# FatLight.net
KiCad netlist of a schematic drawn in EAGLE
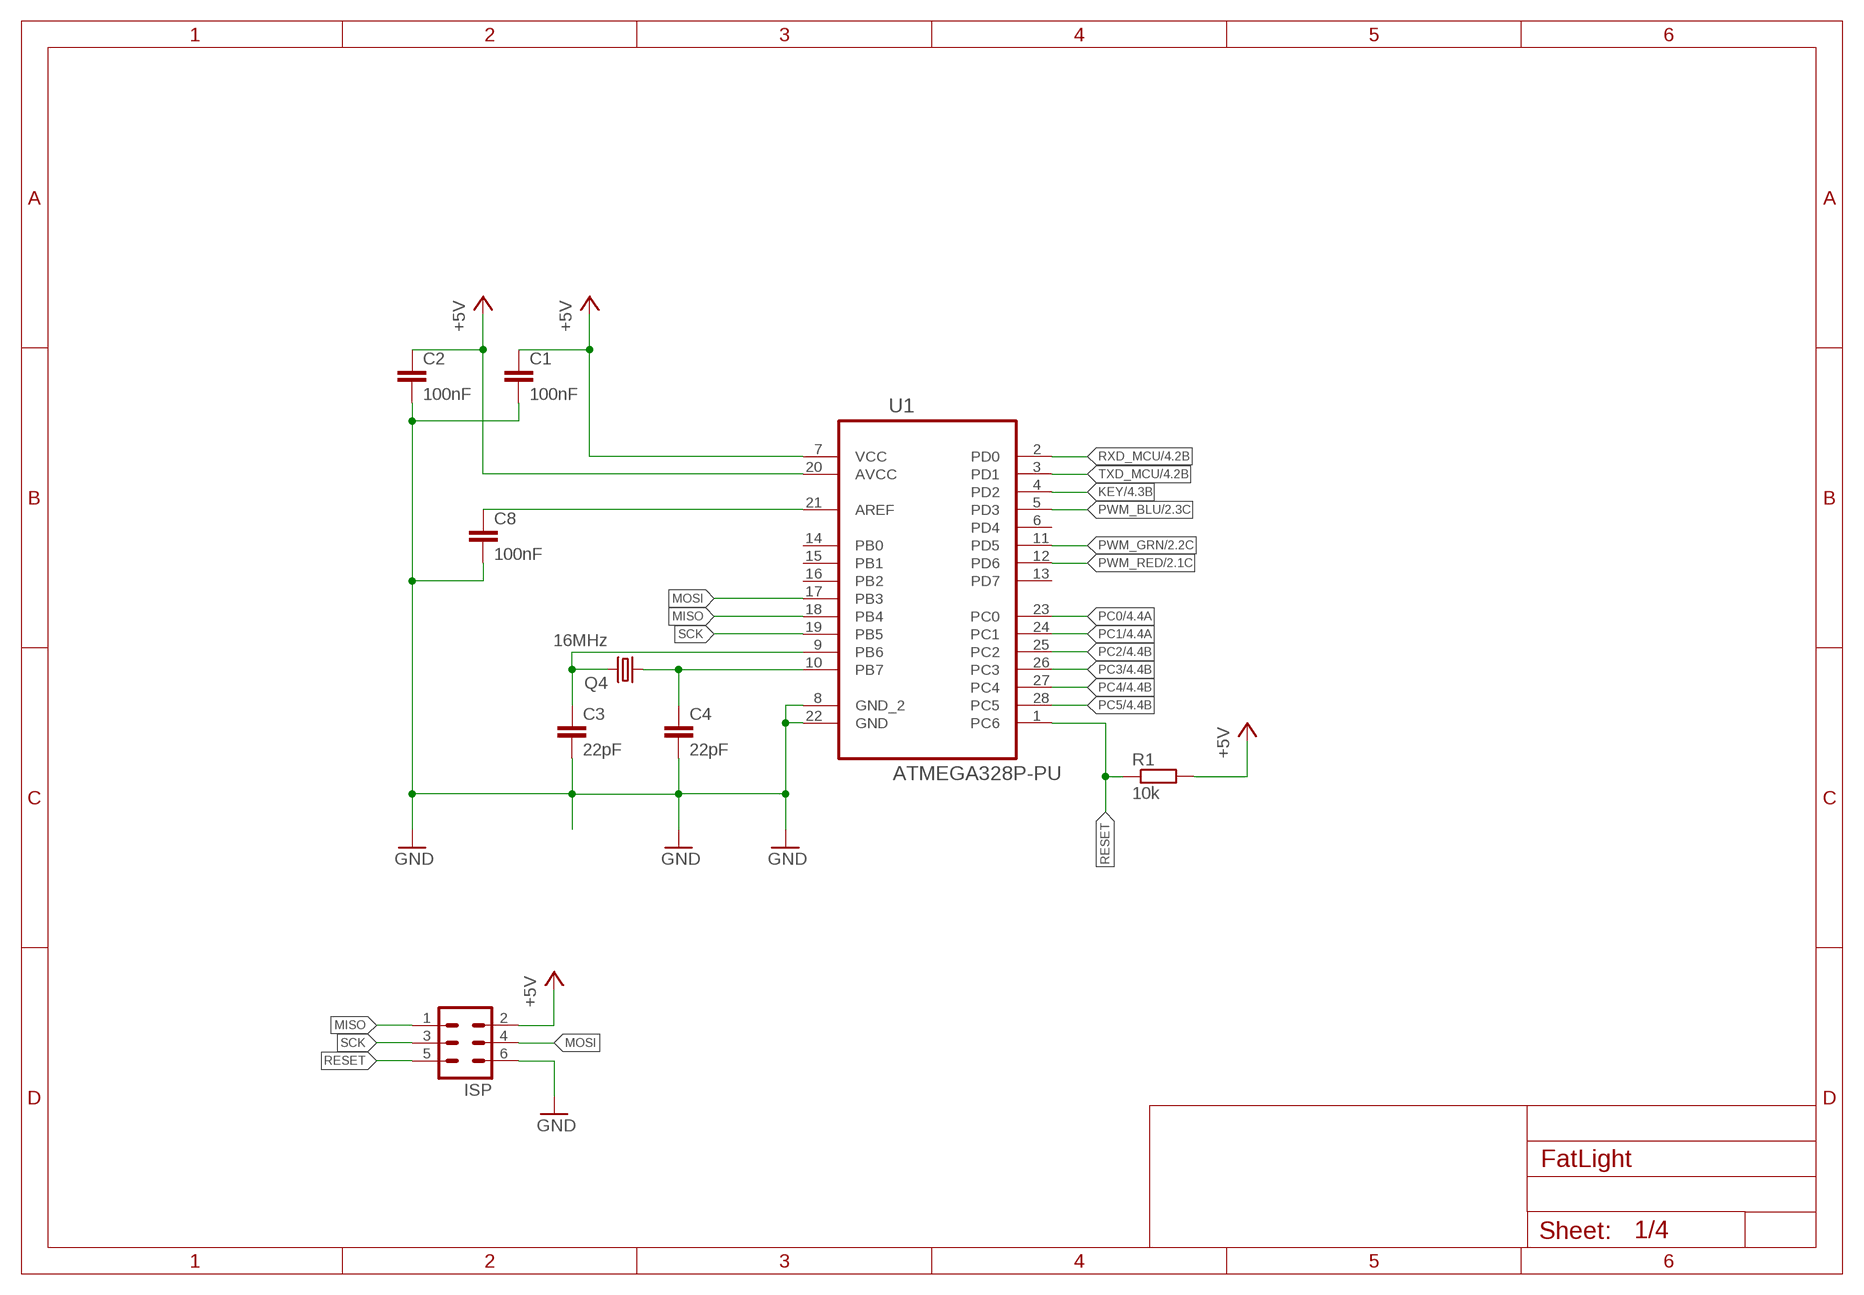
[diagram p0: schematic, sheet 1]
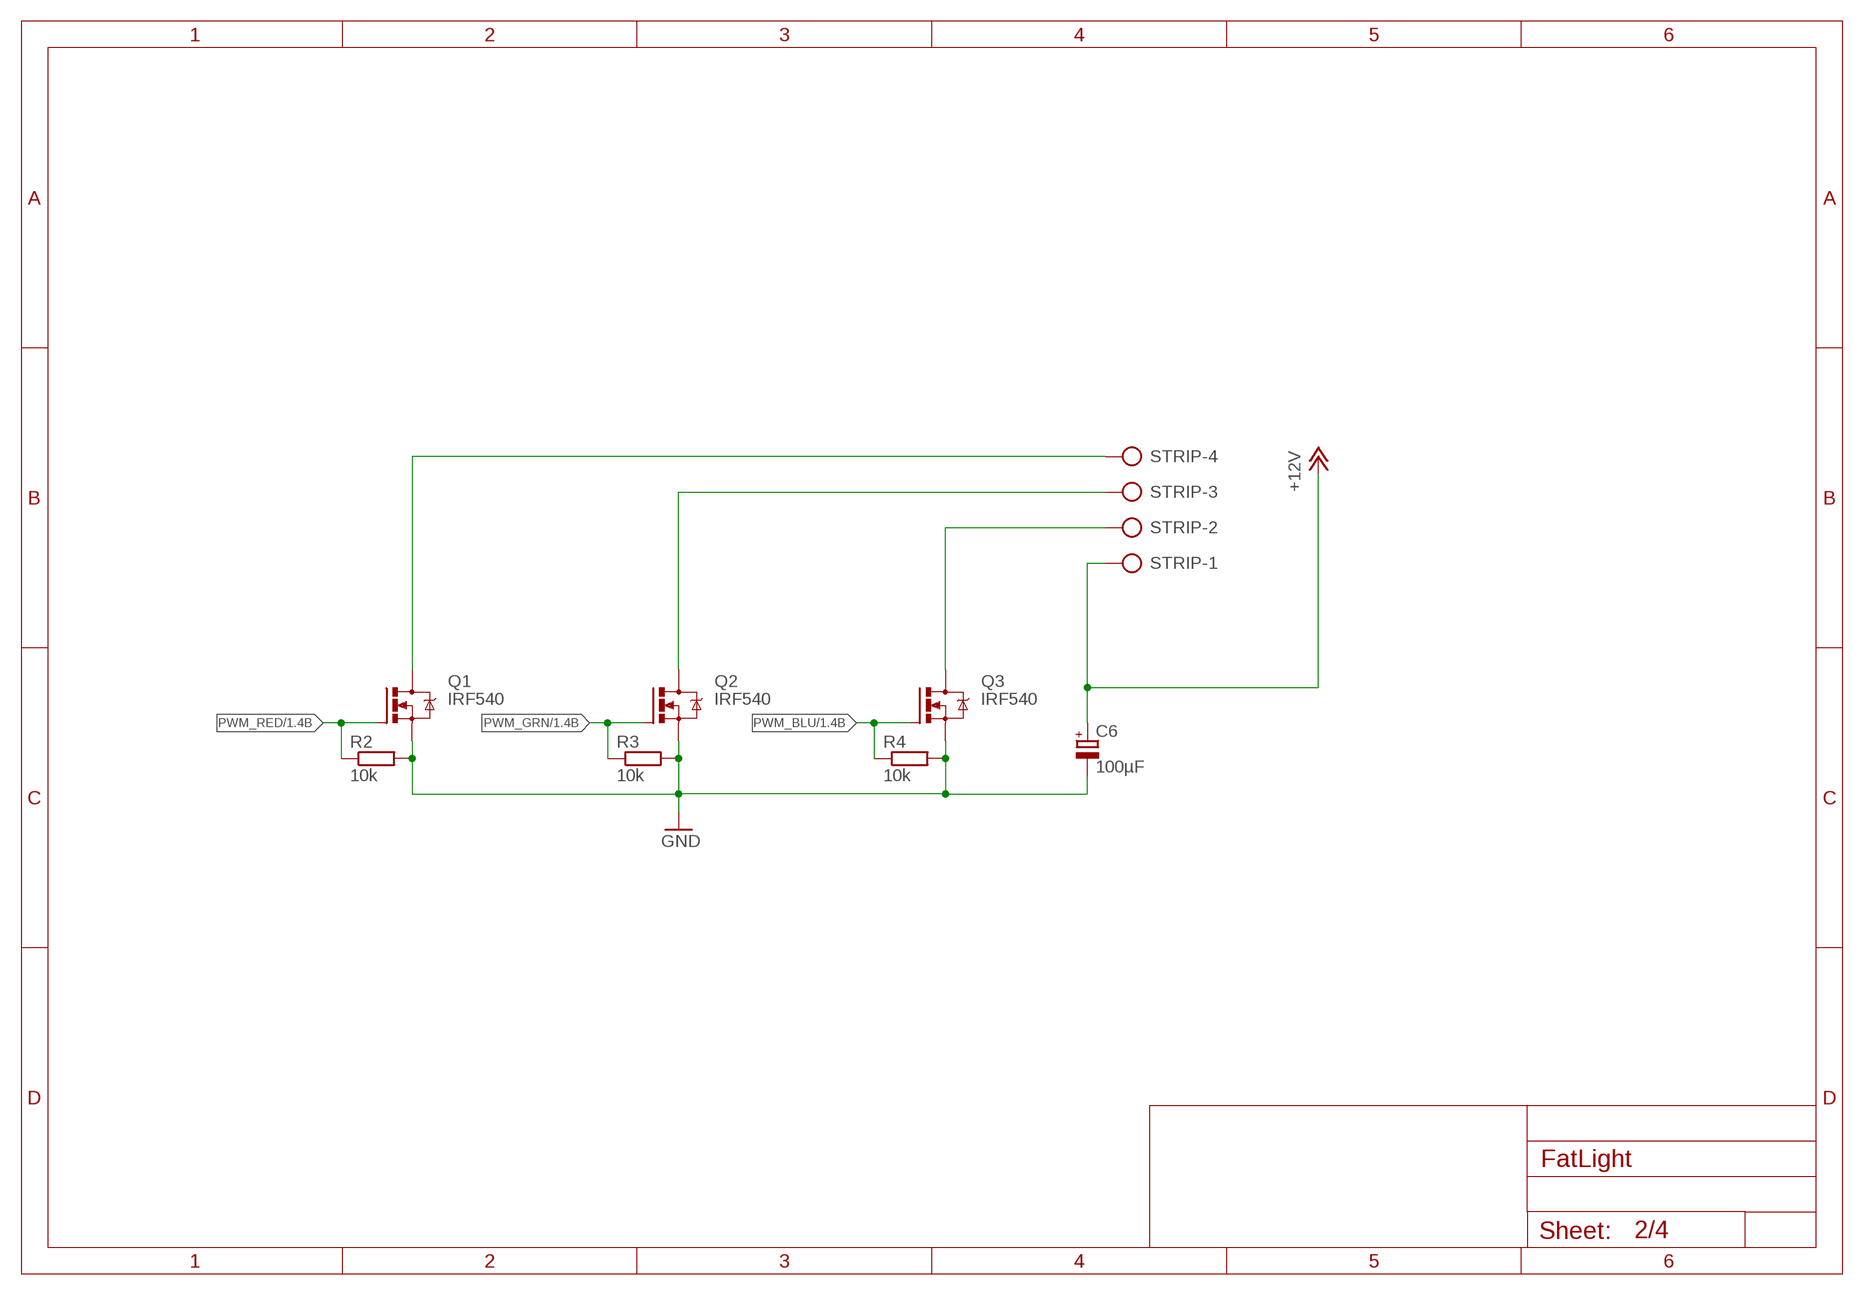
[diagram p1: schematic, sheet 2]
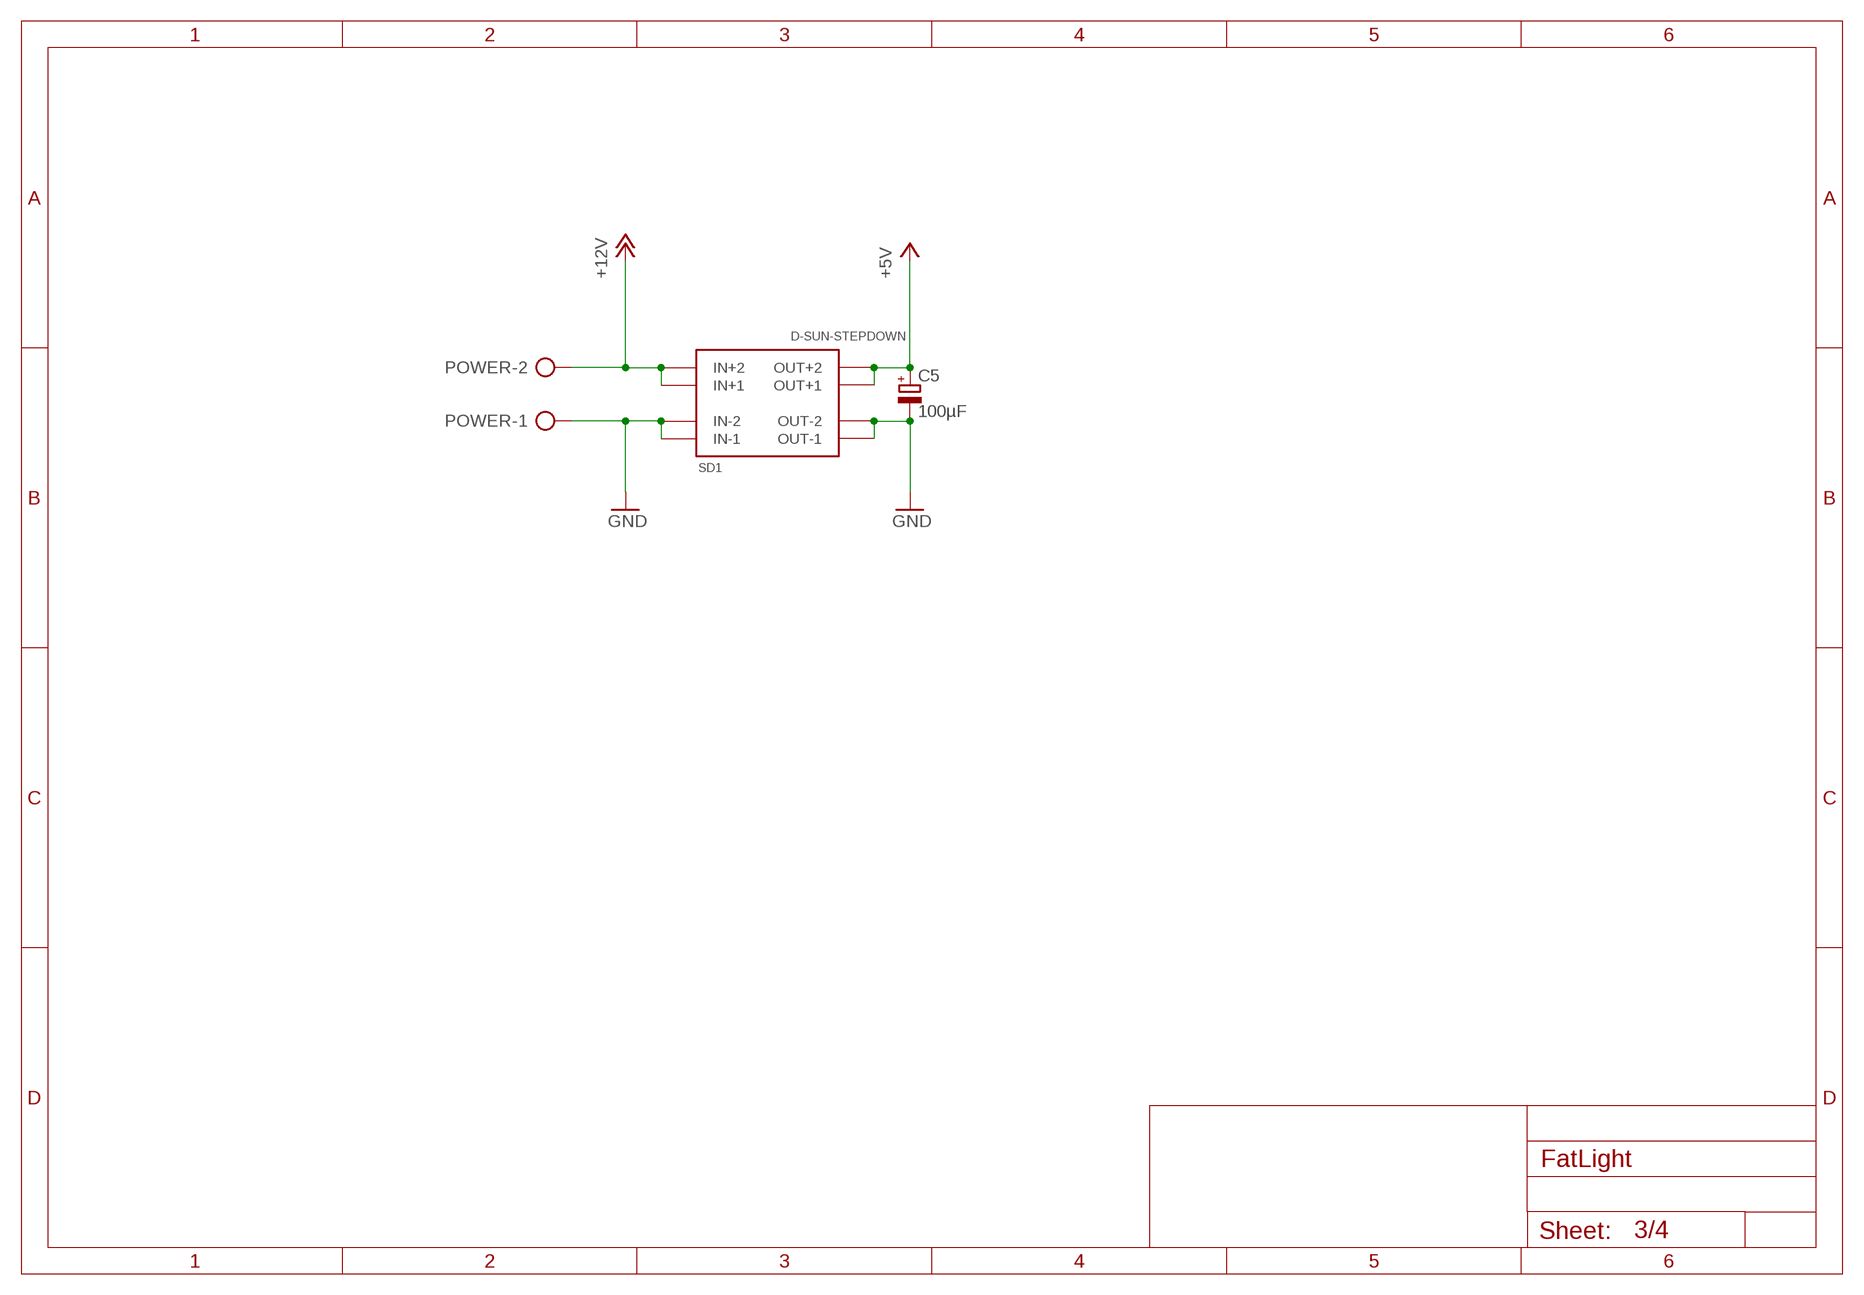
[diagram p2: schematic, sheet 3]
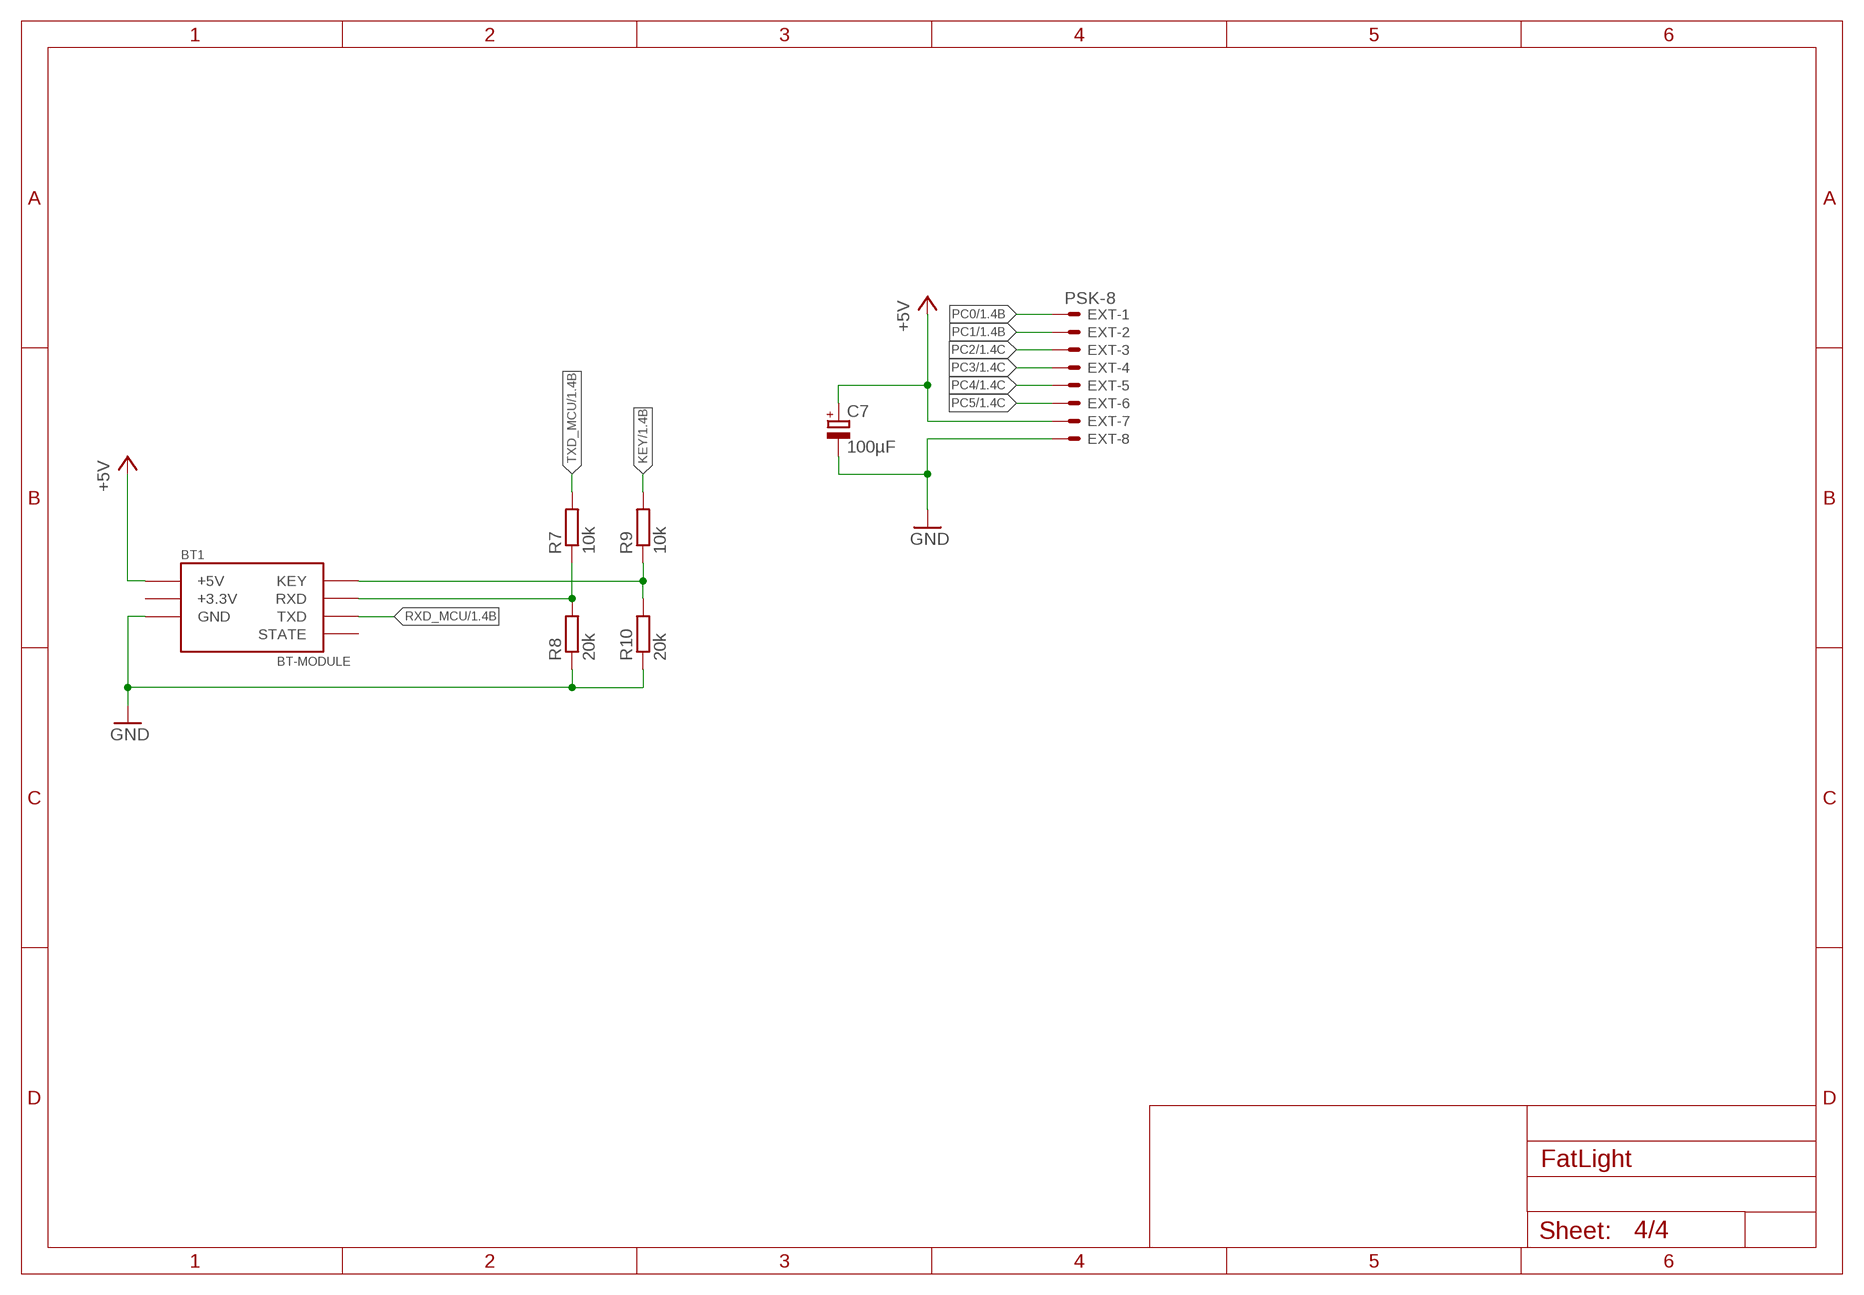
[diagram p3: schematic, sheet 4]

(export (version "E")
  (design (tool "Eeschema 10.0.6"))
  (components
    (comp (ref "BT1")
      (value "BT-MODULE")
      (footprint "eagle-import:HC-05-6PIN")
      (libsource (lib "eagle-import") (part "BT-MODULE"))
    )
    (comp (ref "C7")
      (value "100µF")
      (footprint "eagle-import:E2,5-5")
      (libsource (lib "eagle-import") (part "CPOL-EUE2.5-5"))
    )
    (comp (ref "EXT")
      (value "PSK-8")
      (footprint "eagle-import:22-23-2081")
      (fields (field (name "MF") "MOLEX") (field (name "MPN") "22-23-2081"))
      (libsource (lib "eagle-import") (part "22-23-2081"))
    )
    (comp (ref "R7")
      (value "10k")
      (footprint "eagle-import:0207_7")
      (libsource (lib "eagle-import") (part "R-EU_0207/7"))
    )
    (comp (ref "R8")
      (value "20k")
      (footprint "eagle-import:0207_7")
      (libsource (lib "eagle-import") (part "R-EU_0207/7"))
    )
    (comp (ref "R9")
      (value "10k")
      (footprint "eagle-import:0207_7")
      (libsource (lib "eagle-import") (part "R-EU_0207/7"))
    )
    (comp (ref "R10")
      (value "20k")
      (footprint "eagle-import:0207_7")
      (libsource (lib "eagle-import") (part "R-EU_0207/7"))
    )
    (comp (ref "C1")
      (value "100nF")
      (footprint "eagle-import:C025-025X050")
      (libsource (lib "eagle-import") (part "C-EU025-025X050"))
    )
    (comp (ref "C2")
      (value "100nF")
      (footprint "eagle-import:C025-025X050")
      (libsource (lib "eagle-import") (part "C-EU025-025X050"))
    )
    (comp (ref "C3")
      (value "22pF")
      (footprint "eagle-import:C025-025X050")
      (libsource (lib "eagle-import") (part "C-EU025-025X050"))
    )
    (comp (ref "C4")
      (value "22pF")
      (footprint "eagle-import:C025-025X050")
      (libsource (lib "eagle-import") (part "C-EU025-025X050"))
    )
    (comp (ref "C8")
      (value "100nF")
      (footprint "eagle-import:C025-025X050")
      (libsource (lib "eagle-import") (part "C-EU025-025X050"))
    )
    (comp (ref "ISP")
      (value "ML6")
      (footprint "eagle-import:ML6")
      (libsource (lib "eagle-import") (part "ML6"))
    )
    (comp (ref "Q4")
      (value "16MHz")
      (footprint "eagle-import:HC49_S")
      (libsource (lib "eagle-import") (part "CRYSTALHC49S"))
    )
    (comp (ref "R1")
      (value "10k")
      (footprint "eagle-import:0207_7")
      (libsource (lib "eagle-import") (part "R-EU_0207/7"))
    )
    (comp (ref "U1")
      (value "ATMEGA328P-PU")
      (footprint "eagle-import:DIP254P762X457-28")
      (libsource (lib "eagle-import") (part "ATMEGA328P-PU"))
    )
    (comp (ref "C5")
      (value "100µF")
      (footprint "eagle-import:E2,5-5")
      (libsource (lib "eagle-import") (part "CPOL-EUE2.5-5"))
    )
    (comp (ref "POWER")
      (value "AK500/2")
      (footprint "eagle-import:AK500_2")
      (libsource (lib "eagle-import") (part "AK500/2"))
    )
    (comp (ref "SD1")
      (value "D-SUN-STEPDOWN")
      (footprint "eagle-import:STEPDOWN-21X16")
      (libsource (lib "eagle-import") (part "D-SUN-STEPDOWN"))
    )
    (comp (ref "C6")
      (value "100µF")
      (footprint "eagle-import:E2,5-5")
      (libsource (lib "eagle-import") (part "CPOL-EUE2.5-5"))
    )
    (comp (ref "Q1")
      (value "IRF540")
      (footprint "eagle-import:TO220BV")
      (libsource (lib "eagle-import") (part "IRF540"))
    )
    (comp (ref "Q2")
      (value "IRF540")
      (footprint "eagle-import:TO220BV")
      (libsource (lib "eagle-import") (part "IRF540"))
    )
    (comp (ref "Q3")
      (value "IRF540")
      (footprint "eagle-import:TO220BV")
      (libsource (lib "eagle-import") (part "IRF540"))
    )
    (comp (ref "R2")
      (value "10k")
      (footprint "eagle-import:0207_7")
      (libsource (lib "eagle-import") (part "R-EU_0207/7"))
    )
    (comp (ref "R3")
      (value "10k")
      (footprint "eagle-import:0207_7")
      (libsource (lib "eagle-import") (part "R-EU_0207/7"))
    )
    (comp (ref "R4")
      (value "10k")
      (footprint "eagle-import:0207_7")
      (libsource (lib "eagle-import") (part "R-EU_0207/7"))
    )
    (comp (ref "STRIP")
      (value "AK500/4")
      (footprint "eagle-import:AK500_4")
      (libsource (lib "eagle-import") (part "AK500/4"))
    )
  )
  (nets
    (net (code "1") (name "+3.3V") (class "Default")
      (node (ref "BT1") (pin "+3.3V") (pinfunction "+3.3V_+3.3V") (pintype "power_in"))
    )
    (net (code "2") (name "+5V") (class "Default")
      (node (ref "BT1") (pin "+5V") (pinfunction "+5V_+5V") (pintype "power_in"))
      (node (ref "BT1") (pin "+5V1") (pinfunction "+5V_+5V1") (pintype "power_in"))
      (node (ref "C1") (pin "1") (pinfunction "1_1") (pintype "passive"))
      (node (ref "C2") (pin "1") (pinfunction "1_1") (pintype "passive"))
      (node (ref "C5") (pin "+") (pinfunction "+_+") (pintype "passive"))
      (node (ref "C7") (pin "+") (pinfunction "+_+") (pintype "passive"))
      (node (ref "EXT") (pin "7") (pinfunction "S_7") (pintype "passive"))
      (node (ref "ISP") (pin "2") (pinfunction "2_2") (pintype "passive"))
      (node (ref "R1") (pin "2") (pinfunction "2_2") (pintype "passive"))
      (node (ref "SD1") (pin "OUT+1") (pinfunction "OUT+1_OUT+1") (pintype "power_in"))
      (node (ref "SD1") (pin "OUT+2") (pinfunction "OUT+2_OUT+2") (pintype "power_in"))
      (node (ref "U1") (pin "20") (pinfunction "AVCC_20") (pintype "power_in"))
      (node (ref "U1") (pin "7") (pinfunction "VCC_7") (pintype "power_in"))
    )
    (net (code "3") (name "+12V") (class "Default")
      (node (ref "C6") (pin "+") (pinfunction "+_+") (pintype "passive"))
      (node (ref "POWER") (pin "2") (pinfunction "KL_2") (pintype "passive"))
      (node (ref "SD1") (pin "IN+1") (pinfunction "IN+1_IN+1") (pintype "power_in"))
      (node (ref "SD1") (pin "IN+2") (pinfunction "IN+2_IN+2") (pintype "power_in"))
      (node (ref "STRIP") (pin "1") (pinfunction "KL_1") (pintype "passive"))
    )
    (net (code "4") (name "GND") (class "Default")
      (node (ref "BT1") (pin "GND") (pinfunction "GND_GND") (pintype "power_in"))
      (node (ref "BT1") (pin "GND1") (pinfunction "GND_GND1") (pintype "power_in"))
      (node (ref "C1") (pin "2") (pinfunction "2_2") (pintype "passive"))
      (node (ref "C2") (pin "2") (pinfunction "2_2") (pintype "passive"))
      (node (ref "C3") (pin "2") (pinfunction "2_2") (pintype "passive"))
      (node (ref "C4") (pin "2") (pinfunction "2_2") (pintype "passive"))
      (node (ref "C5") (pin "-") (pinfunction "-_-") (pintype "passive"))
      (node (ref "C6") (pin "-") (pinfunction "-_-") (pintype "passive"))
      (node (ref "C7") (pin "-") (pinfunction "-_-") (pintype "passive"))
      (node (ref "C8") (pin "2") (pinfunction "2_2") (pintype "passive"))
      (node (ref "EXT") (pin "8") (pinfunction "S_8") (pintype "passive"))
      (node (ref "ISP") (pin "6") (pinfunction "6_6") (pintype "passive"))
      (node (ref "POWER") (pin "1") (pinfunction "KL_1") (pintype "passive"))
      (node (ref "Q1") (pin "S") (pinfunction "S_S") (pintype "passive"))
      (node (ref "Q2") (pin "S") (pinfunction "S_S") (pintype "passive"))
      (node (ref "Q3") (pin "S") (pinfunction "S_S") (pintype "passive"))
      (node (ref "R10") (pin "1") (pinfunction "1_1") (pintype "passive"))
      (node (ref "R2") (pin "2") (pinfunction "2_2") (pintype "passive"))
      (node (ref "R3") (pin "2") (pinfunction "2_2") (pintype "passive"))
      (node (ref "R4") (pin "2") (pinfunction "2_2") (pintype "passive"))
      (node (ref "R8") (pin "1") (pinfunction "1_1") (pintype "passive"))
      (node (ref "SD1") (pin "IN-1") (pinfunction "IN-1_IN-1") (pintype "power_in"))
      (node (ref "SD1") (pin "IN-2") (pinfunction "IN-2_IN-2") (pintype "power_in"))
      (node (ref "SD1") (pin "OUT-1") (pinfunction "OUT-1_OUT-1") (pintype "power_in"))
      (node (ref "SD1") (pin "OUT-2") (pinfunction "OUT-2_OUT-2") (pintype "power_in"))
      (node (ref "U1") (pin "22") (pinfunction "GND_22") (pintype "passive"))
      (node (ref "U1") (pin "8") (pinfunction "GND_2_8") (pintype "passive"))
    )
    (net (code "5") (name "KEY") (class "Default")
      (node (ref "R9") (pin "2") (pinfunction "2_2") (pintype "passive"))
      (node (ref "U1") (pin "4") (pinfunction "PD2_4") (pintype "bidirectional"))
    )
    (net (code "6") (name "MISO") (class "Default")
      (node (ref "ISP") (pin "1") (pinfunction "1_1") (pintype "passive"))
      (node (ref "U1") (pin "18") (pinfunction "PB4_18") (pintype "bidirectional"))
    )
    (net (code "7") (name "MOSI") (class "Default")
      (node (ref "ISP") (pin "4") (pinfunction "4_4") (pintype "passive"))
      (node (ref "U1") (pin "17") (pinfunction "PB3_17") (pintype "bidirectional"))
    )
    (net (code "8") (name "Net-(BT1-KEY-PadKEY1)") (class "Default")
      (node (ref "BT1") (pin "KEY") (pinfunction "KEY_KEY") (pintype "input"))
      (node (ref "BT1") (pin "KEY1") (pinfunction "KEY_KEY1") (pintype "input"))
      (node (ref "R10") (pin "2") (pinfunction "2_2") (pintype "passive"))
      (node (ref "R9") (pin "1") (pinfunction "1_1") (pintype "passive"))
    )
    (net (code "9") (name "Net-(BT1-PadRXD)") (class "Default")
      (node (ref "BT1") (pin "RXD") (pinfunction "RXD_RXD") (pintype "input"))
      (node (ref "BT1") (pin "RXD1") (pinfunction "RXD_RXD1") (pintype "input"))
      (node (ref "R7") (pin "1") (pinfunction "1_1") (pintype "passive"))
      (node (ref "R8") (pin "2") (pinfunction "2_2") (pintype "passive"))
    )
    (net (code "10") (name "Net-(STRIPB-KL)") (class "Default")
      (node (ref "Q3") (pin "D") (pinfunction "D_D") (pintype "passive"))
      (node (ref "STRIP") (pin "2") (pinfunction "KL_2") (pintype "passive"))
    )
    (net (code "11") (name "Net-(STRIPC-KL)") (class "Default")
      (node (ref "Q2") (pin "D") (pinfunction "D_D") (pintype "passive"))
      (node (ref "STRIP") (pin "3") (pinfunction "KL_3") (pintype "passive"))
    )
    (net (code "12") (name "Net-(STRIPD-KL)") (class "Default")
      (node (ref "Q1") (pin "D") (pinfunction "D_D") (pintype "passive"))
      (node (ref "STRIP") (pin "4") (pinfunction "KL_4") (pintype "passive"))
    )
    (net (code "13") (name "Net-(U1-AREF)") (class "Default")
      (node (ref "C8") (pin "1") (pinfunction "1_1") (pintype "passive"))
      (node (ref "U1") (pin "21") (pinfunction "AREF_21") (pintype "input"))
    )
    (net (code "14") (name "Net-(U1-PB6)") (class "Default")
      (node (ref "C3") (pin "1") (pinfunction "1_1") (pintype "passive"))
      (node (ref "Q4") (pin "2") (pinfunction "2_2") (pintype "passive"))
      (node (ref "U1") (pin "9") (pinfunction "PB6_9") (pintype "bidirectional"))
    )
    (net (code "15") (name "Net-(U1-PB7)") (class "Default")
      (node (ref "C4") (pin "1") (pinfunction "1_1") (pintype "passive"))
      (node (ref "Q4") (pin "1") (pinfunction "1_1") (pintype "passive"))
      (node (ref "U1") (pin "10") (pinfunction "PB7_10") (pintype "bidirectional"))
    )
    (net (code "16") (name "PC0") (class "Default")
      (node (ref "EXT") (pin "1") (pinfunction "S_1") (pintype "passive"))
      (node (ref "U1") (pin "23") (pinfunction "PC0_23") (pintype "bidirectional"))
    )
    (net (code "17") (name "PC1") (class "Default")
      (node (ref "EXT") (pin "2") (pinfunction "S_2") (pintype "passive"))
      (node (ref "U1") (pin "24") (pinfunction "PC1_24") (pintype "bidirectional"))
    )
    (net (code "18") (name "PC2") (class "Default")
      (node (ref "EXT") (pin "3") (pinfunction "S_3") (pintype "passive"))
      (node (ref "U1") (pin "25") (pinfunction "PC2_25") (pintype "bidirectional"))
    )
    (net (code "19") (name "PC3") (class "Default")
      (node (ref "EXT") (pin "4") (pinfunction "S_4") (pintype "passive"))
      (node (ref "U1") (pin "26") (pinfunction "PC3_26") (pintype "bidirectional"))
    )
    (net (code "20") (name "PC4") (class "Default")
      (node (ref "EXT") (pin "5") (pinfunction "S_5") (pintype "passive"))
      (node (ref "U1") (pin "27") (pinfunction "PC4_27") (pintype "bidirectional"))
    )
    (net (code "21") (name "PC5") (class "Default")
      (node (ref "EXT") (pin "6") (pinfunction "S_6") (pintype "passive"))
      (node (ref "U1") (pin "28") (pinfunction "PC5_28") (pintype "bidirectional"))
    )
    (net (code "22") (name "PWM_BLU") (class "Default")
      (node (ref "Q3") (pin "G") (pinfunction "G_G") (pintype "passive"))
      (node (ref "R4") (pin "1") (pinfunction "1_1") (pintype "passive"))
      (node (ref "U1") (pin "5") (pinfunction "PD3_5") (pintype "bidirectional"))
    )
    (net (code "23") (name "PWM_GRN") (class "Default")
      (node (ref "Q2") (pin "G") (pinfunction "G_G") (pintype "passive"))
      (node (ref "R3") (pin "1") (pinfunction "1_1") (pintype "passive"))
      (node (ref "U1") (pin "11") (pinfunction "PD5_11") (pintype "bidirectional"))
    )
    (net (code "24") (name "PWM_RED") (class "Default")
      (node (ref "Q1") (pin "G") (pinfunction "G_G") (pintype "passive"))
      (node (ref "R2") (pin "1") (pinfunction "1_1") (pintype "passive"))
      (node (ref "U1") (pin "12") (pinfunction "PD6_12") (pintype "bidirectional"))
    )
    (net (code "25") (name "RESET") (class "Default")
      (node (ref "ISP") (pin "5") (pinfunction "5_5") (pintype "passive"))
      (node (ref "R1") (pin "1") (pinfunction "1_1") (pintype "passive"))
      (node (ref "U1") (pin "1") (pinfunction "PC6_1") (pintype "bidirectional"))
    )
    (net (code "26") (name "RXD_MCU") (class "Default")
      (node (ref "BT1") (pin "TXD") (pinfunction "TXD_TXD") (pintype "output"))
      (node (ref "BT1") (pin "TXD1") (pinfunction "TXD_TXD1") (pintype "output"))
      (node (ref "U1") (pin "2") (pinfunction "PD0_2") (pintype "bidirectional"))
    )
    (net (code "27") (name "SCK") (class "Default")
      (node (ref "ISP") (pin "3") (pinfunction "3_3") (pintype "passive"))
      (node (ref "U1") (pin "19") (pinfunction "PB5_19") (pintype "bidirectional"))
    )
    (net (code "28") (name "TXD_MCU") (class "Default")
      (node (ref "R7") (pin "2") (pinfunction "2_2") (pintype "passive"))
      (node (ref "U1") (pin "3") (pinfunction "PD1_3") (pintype "bidirectional"))
    )
    (net (code "29") (name "unconnected-(BT1-PadSTATE)") (class "Default")
      (node (ref "BT1") (pin "STATE") (pinfunction "STATE_STATE") (pintype "output"))
    )
    (net (code "30") (name "unconnected-(U1-PB0-Pad14)") (class "Default")
      (node (ref "U1") (pin "14") (pinfunction "PB0_14") (pintype "bidirectional"))
    )
    (net (code "31") (name "unconnected-(U1-PB1-Pad15)") (class "Default")
      (node (ref "U1") (pin "15") (pinfunction "PB1_15") (pintype "bidirectional"))
    )
    (net (code "32") (name "unconnected-(U1-PB2-Pad16)") (class "Default")
      (node (ref "U1") (pin "16") (pinfunction "PB2_16") (pintype "bidirectional"))
    )
    (net (code "33") (name "unconnected-(U1-PD4-Pad6)") (class "Default")
      (node (ref "U1") (pin "6") (pinfunction "PD4_6") (pintype "bidirectional"))
    )
    (net (code "34") (name "unconnected-(U1-PD7-Pad13)") (class "Default")
      (node (ref "U1") (pin "13") (pinfunction "PD7_13") (pintype "bidirectional"))
    )
  )
)
